# Microphone-Boards_V1_0_SD18OB261.net
KiCad netlist of a schematic drawn in Altium Designer
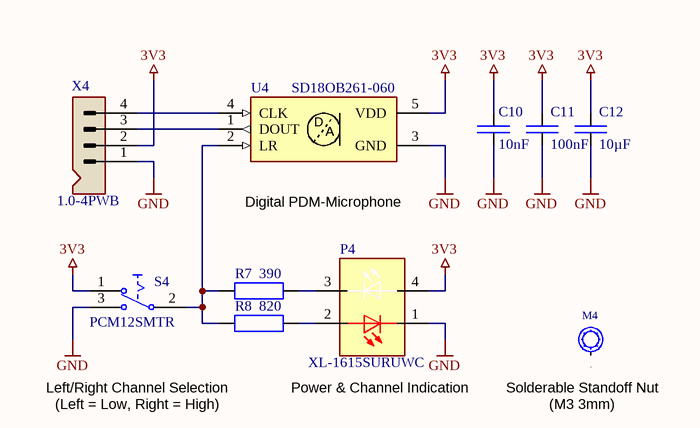
[diagram p0: Microphone-Boards_V1.0_SD18OB261.SchDoc]

(export (version "E")
  (design (tool "Eeschema 10.0.6"))
  (components
    (comp (ref "C10")
      (value "10nF")
      (footprint "SMD Keramikkondensator 0603")
      (description "CAP-MK")
      (libsource (lib "AudioAmp") (part "C-CAPACITOR"))
    )
    (comp (ref "C11")
      (value "100nF")
      (footprint "SMD Keramikkondensator 0603")
      (description "SMD Ceramic Capacitor E6")
      (libsource (lib "Ceramic Capacitors-E6") (part "E6 - 100nF"))
    )
    (comp (ref "C12")
      (value "10µF")
      (footprint "SMD Keramikkondensator 1206")
      (description "SMD Ceramic Capacitor E6")
      (libsource (lib "Ceramic Capacitors-E6") (part "E6 - 10uF"))
    )
    (comp (ref "M4")
      (value "SMTSO-M3-3ET")
      (footprint "SMD Solder-Nut (M3 3mm)")
      (description "Solderable Standoff Nut")
      (libsource (lib "Velotour_2022") (part "M-Spacer_M3_3mm"))
    )
    (comp (ref "P4")
      (value "XL-1615SURUWC")
      (footprint "SMD LED 0606")
      (description "LED Red/White")
      (libsource (lib "Microphone-Boards") (part "P-XL-1615SURUWC"))
    )
    (comp (ref "R7")
      (value "390")
      (footprint "SMD Widerstand 0603")
      (description "SMD-Widerstand 1/4W")
      (libsource (lib "Backplane_1") (part "R-RESISTOR"))
    )
    (comp (ref "R8")
      (value "820")
      (footprint "SMD Widerstand 0603")
      (description "SMD-Widerstand 1/4W")
      (libsource (lib "Backplane_1") (part "R-RESISTOR"))
    )
    (comp (ref "S4")
      (value "PCM12SMTR")
      (footprint "SMD Switch SPDT (PCM12SMTR)")
      (description "Miniature Slide Switch")
      (libsource (lib "Custom ST-Link") (part "S-PCM12SMTR"))
    )
    (comp (ref "U4")
      (value "SD18OB261-060")
      (footprint "SMD Microphone (SD18OB261-060)")
      (description "Digital PDM MEMS Microphone (Bottom Port)")
      (libsource (lib "Microphone-Boards") (part "U-SD18OB261-060"))
    )
    (comp (ref "X4")
      (value "1.0-4PWB")
      (footprint "SMD Connector (SM04B-SRSS-TB)")
      (description "Wire To Board Connector (1x4P 1.0mm)")
      (libsource (lib "Audio-Beamformer") (part "X-Stiftleiste (4-Fach)"))
    )
  )
  (nets
    (net (code "1") (name "/M") (class "Default")
      (node (ref "M4") (pin "1") (pinfunction "1_1") (pintype "passive"))
    )
    (net (code "2") (name "3V3") (class "Default")
      (node (ref "C10") (pin "2") (pinfunction "2_2") (pintype "passive"))
      (node (ref "C11") (pin "2") (pinfunction "2_2") (pintype "passive"))
      (node (ref "C12") (pin "2") (pinfunction "2_2") (pintype "passive"))
      (node (ref "P4") (pin "4") (pinfunction "WA_4") (pintype "passive"))
      (node (ref "S4") (pin "1") (pinfunction "NC1_1") (pintype "passive"))
      (node (ref "U4") (pin "5") (pinfunction "VDD_5") (pintype "power_in"))
      (node (ref "X4") (pin "2") (pinfunction "2_2") (pintype "passive"))
    )
    (net (code "3") (name "GND") (class "Default")
      (node (ref "C10") (pin "1") (pinfunction "1_1") (pintype "passive"))
      (node (ref "C11") (pin "1") (pinfunction "1_1") (pintype "passive"))
      (node (ref "C12") (pin "1") (pinfunction "1_1") (pintype "passive"))
      (node (ref "P4") (pin "1") (pinfunction "RC_1") (pintype "passive"))
      (node (ref "S4") (pin "3") (pinfunction "NO1_3") (pintype "passive"))
      (node (ref "U4") (pin "3") (pinfunction "GND_3") (pintype "power_in"))
      (node (ref "X4") (pin "1") (pinfunction "1_1") (pintype "passive"))
    )
    (net (code "4") (name "Net-(P4-RA)") (class "Default")
      (node (ref "P4") (pin "2") (pinfunction "RA_2") (pintype "passive"))
      (node (ref "R8") (pin "2") (pinfunction "2_2") (pintype "passive"))
    )
    (net (code "5") (name "Net-(P4-WC)") (class "Default")
      (node (ref "P4") (pin "3") (pinfunction "WC_3") (pintype "passive"))
      (node (ref "R7") (pin "2") (pinfunction "2_2") (pintype "passive"))
    )
    (net (code "6") (name "Net-(S4-COMMON1)") (class "Default")
      (node (ref "R7") (pin "1") (pinfunction "1_1") (pintype "passive"))
      (node (ref "R8") (pin "1") (pinfunction "1_1") (pintype "passive"))
      (node (ref "S4") (pin "2") (pinfunction "COMMON1_2") (pintype "passive"))
      (node (ref "U4") (pin "2") (pinfunction "LR_2") (pintype "input"))
    )
    (net (code "7") (name "Net-(U4-CLK)") (class "Default")
      (node (ref "U4") (pin "4") (pinfunction "CLK_4") (pintype "input"))
      (node (ref "X4") (pin "4") (pinfunction "4_4") (pintype "passive"))
    )
    (net (code "8") (name "Net-(U4-DOUT)") (class "Default")
      (node (ref "U4") (pin "1") (pinfunction "DOUT_1") (pintype "output"))
      (node (ref "X4") (pin "3") (pinfunction "3_3") (pintype "passive"))
    )
  )
)
